# Nodino-CM4.net
KiCad netlist of a schematic drawn in EAGLE
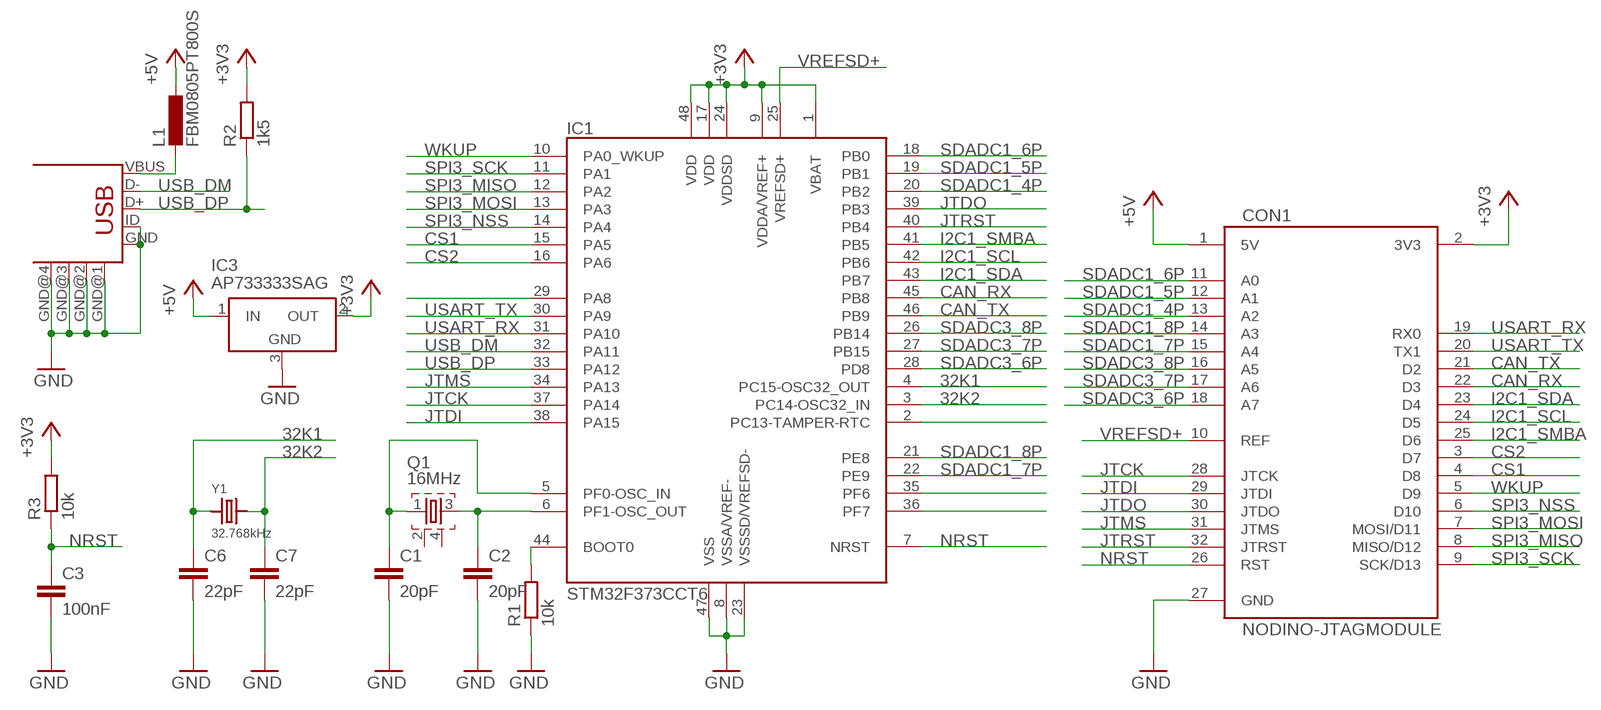
[diagram p0: schematic, sheet 1]

(export (version "E")
  (design (tool "Eeschema 10.0.6"))
  (components
    (comp (ref "C1")
      (value "20pF")
      (footprint "eagle-import:C0603K")
      (libsource (lib "eagle-import") (part "C-EUC0603K"))
    )
    (comp (ref "C2")
      (value "20pF")
      (footprint "eagle-import:C0603K")
      (libsource (lib "eagle-import") (part "C-EUC0603K"))
    )
    (comp (ref "C3")
      (value "100nF")
      (footprint "eagle-import:C0603K")
      (libsource (lib "eagle-import") (part "C-EUC0603K"))
    )
    (comp (ref "C6")
      (value "22pF")
      (footprint "eagle-import:C0603K")
      (libsource (lib "eagle-import") (part "C-EUC0603K"))
    )
    (comp (ref "C7")
      (value "22pF")
      (footprint "eagle-import:C0603K")
      (libsource (lib "eagle-import") (part "C-EUC0603K"))
    )
    (comp (ref "CON1")
      (value "NODINO-JTAGMODULE")
      (footprint "eagle-import:NODINO-JTAG-MOD")
      (libsource (lib "eagle-import") (part "NODINO-JTAGMODULE"))
    )
    (comp (ref "CON2")
      (value "USB-OTG_SHIELD")
      (footprint "eagle-import:USB-UAB-S1")
      (libsource (lib "eagle-import") (part "USB-OTG_SHIELD"))
    )
    (comp (ref "IC1")
      (value "STM32F373CCT6")
      (footprint "eagle-import:LQFP48")
      (libsource (lib "eagle-import") (part "STM32F373CCT6"))
    )
    (comp (ref "IC3")
      (value "AP733333SAG")
      (footprint "eagle-import:SOT23")
      (libsource (lib "eagle-import") (part "AP733333SAG"))
    )
    (comp (ref "L1")
      (value "FBM0805PT800S")
      (footprint "eagle-import:L0805")
      (libsource (lib "eagle-import") (part "L-EUL0805"))
    )
    (comp (ref "Q1")
      (value "16MHz")
      (footprint "eagle-import:FA-20H")
      (libsource (lib "eagle-import") (part "FA-20H"))
    )
    (comp (ref "R1")
      (value "10k")
      (footprint "eagle-import:R0603K")
      (libsource (lib "eagle-import") (part "R-EU_R0603K"))
    )
    (comp (ref "R2")
      (value "1k5")
      (footprint "eagle-import:R0603K")
      (libsource (lib "eagle-import") (part "R-EU_R0603K"))
    )
    (comp (ref "R3")
      (value "10k")
      (footprint "eagle-import:R0603K")
      (libsource (lib "eagle-import") (part "R-EU_R0603K"))
    )
    (comp (ref "Y1")
      (value "32.768kHz")
      (footprint "eagle-import:ABS07")
      (libsource (lib "eagle-import") (part "CRYSTAL.ABS07"))
    )
  )
  (nets
    (net (code "1") (name "+3V3") (class "Default")
      (node (ref "CON1") (pin "2") (pinfunction "3V3_2") (pintype "bidirectional"))
      (node (ref "IC1") (pin "1") (pinfunction "VBAT_1") (pintype "power_in"))
      (node (ref "IC1") (pin "17") (pinfunction "VDD_17") (pintype "power_in"))
      (node (ref "IC1") (pin "24") (pinfunction "VDDSD_24") (pintype "power_in"))
      (node (ref "IC1") (pin "48") (pinfunction "VDD_48") (pintype "power_in"))
      (node (ref "IC1") (pin "9") (pinfunction "VDDA/VREF+_9") (pintype "power_in"))
      (node (ref "IC3") (pin "2") (pinfunction "OUT_2") (pintype "output"))
      (node (ref "R2") (pin "2") (pinfunction "2_2") (pintype "passive"))
      (node (ref "R3") (pin "2") (pinfunction "2_2") (pintype "passive"))
    )
    (net (code "2") (name "+5V") (class "Default")
      (node (ref "CON1") (pin "1") (pinfunction "5V_1") (pintype "bidirectional"))
      (node (ref "IC3") (pin "1") (pinfunction "IN_1") (pintype "input"))
      (node (ref "L1") (pin "1") (pinfunction "1_1") (pintype "passive"))
    )
    (net (code "3") (name "/32K1") (class "Default")
      (node (ref "C6") (pin "1") (pinfunction "1_1") (pintype "passive"))
      (node (ref "IC1") (pin "4") (pinfunction "PC15-OSC32_OUT_4") (pintype "input"))
      (node (ref "Y1") (pin "1") (pinfunction "1_1") (pintype "passive"))
    )
    (net (code "4") (name "/32K2") (class "Default")
      (node (ref "C7") (pin "1") (pinfunction "1_1") (pintype "passive"))
      (node (ref "IC1") (pin "3") (pinfunction "PC14-OSC32_IN_3") (pintype "input"))
      (node (ref "Y1") (pin "2") (pinfunction "2_2") (pintype "passive"))
    )
    (net (code "5") (name "/CAN_RX") (class "Default")
      (node (ref "CON1") (pin "22") (pinfunction "D3_22") (pintype "bidirectional"))
      (node (ref "IC1") (pin "45") (pinfunction "PB8_45") (pintype "bidirectional"))
    )
    (net (code "6") (name "/CAN_TX") (class "Default")
      (node (ref "CON1") (pin "21") (pinfunction "D2_21") (pintype "bidirectional"))
      (node (ref "IC1") (pin "46") (pinfunction "PB9_46") (pintype "input"))
    )
    (net (code "7") (name "/CS1") (class "Default")
      (node (ref "CON1") (pin "4") (pinfunction "D8_4") (pintype "bidirectional"))
      (node (ref "IC1") (pin "15") (pinfunction "PA5_15") (pintype "bidirectional"))
    )
    (net (code "8") (name "/CS2") (class "Default")
      (node (ref "CON1") (pin "3") (pinfunction "D7_3") (pintype "bidirectional"))
      (node (ref "IC1") (pin "16") (pinfunction "PA6_16") (pintype "bidirectional"))
    )
    (net (code "9") (name "/I2C1_SCL") (class "Default")
      (node (ref "CON1") (pin "24") (pinfunction "D5_24") (pintype "bidirectional"))
      (node (ref "IC1") (pin "42") (pinfunction "PB6_42") (pintype "input"))
    )
    (net (code "10") (name "/I2C1_SDA") (class "Default")
      (node (ref "CON1") (pin "23") (pinfunction "D4_23") (pintype "bidirectional"))
      (node (ref "IC1") (pin "43") (pinfunction "PB7_43") (pintype "bidirectional"))
    )
    (net (code "11") (name "/I2C1_SMBA") (class "Default")
      (node (ref "CON1") (pin "25") (pinfunction "D6_25") (pintype "bidirectional"))
      (node (ref "IC1") (pin "41") (pinfunction "PB5_41") (pintype "input"))
    )
    (net (code "12") (name "/JTCK") (class "Default")
      (node (ref "CON1") (pin "28") (pinfunction "JTCK_28") (pintype "bidirectional"))
      (node (ref "IC1") (pin "37") (pinfunction "PA14_37") (pintype "bidirectional"))
    )
    (net (code "13") (name "/JTDI") (class "Default")
      (node (ref "CON1") (pin "29") (pinfunction "JTDI_29") (pintype "bidirectional"))
      (node (ref "IC1") (pin "38") (pinfunction "PA15_38") (pintype "bidirectional"))
    )
    (net (code "14") (name "/JTDO") (class "Default")
      (node (ref "CON1") (pin "30") (pinfunction "JTDO_30") (pintype "bidirectional"))
      (node (ref "IC1") (pin "39") (pinfunction "PB3_39") (pintype "bidirectional"))
    )
    (net (code "15") (name "/JTMS") (class "Default")
      (node (ref "CON1") (pin "31") (pinfunction "JTMS_31") (pintype "bidirectional"))
      (node (ref "IC1") (pin "34") (pinfunction "PA13_34") (pintype "bidirectional"))
    )
    (net (code "16") (name "/JTRST") (class "Default")
      (node (ref "CON1") (pin "32") (pinfunction "JTRST_32") (pintype "bidirectional"))
      (node (ref "IC1") (pin "40") (pinfunction "PB4_40") (pintype "bidirectional"))
    )
    (net (code "17") (name "/NRST") (class "Default")
      (node (ref "C3") (pin "1") (pinfunction "1_1") (pintype "passive"))
      (node (ref "CON1") (pin "26") (pinfunction "RST_26") (pintype "bidirectional"))
      (node (ref "IC1") (pin "7") (pinfunction "NRST_7") (pintype "input"))
      (node (ref "R3") (pin "1") (pinfunction "1_1") (pintype "passive"))
    )
    (net (code "18") (name "/SDADC1_4P") (class "Default")
      (node (ref "CON1") (pin "13") (pinfunction "A2_13") (pintype "bidirectional"))
      (node (ref "IC1") (pin "20") (pinfunction "PB2_20") (pintype "bidirectional"))
    )
    (net (code "19") (name "/SDADC1_5P") (class "Default")
      (node (ref "CON1") (pin "12") (pinfunction "A1_12") (pintype "bidirectional"))
      (node (ref "IC1") (pin "19") (pinfunction "PB1_19") (pintype "bidirectional"))
    )
    (net (code "20") (name "/SDADC1_6P") (class "Default")
      (node (ref "CON1") (pin "11") (pinfunction "A0_11") (pintype "bidirectional"))
      (node (ref "IC1") (pin "18") (pinfunction "PB0_18") (pintype "bidirectional"))
    )
    (net (code "21") (name "/SDADC1_7P") (class "Default")
      (node (ref "CON1") (pin "15") (pinfunction "A4_15") (pintype "bidirectional"))
      (node (ref "IC1") (pin "22") (pinfunction "PE9_22") (pintype "input"))
    )
    (net (code "22") (name "/SDADC1_8P") (class "Default")
      (node (ref "CON1") (pin "14") (pinfunction "A3_14") (pintype "bidirectional"))
      (node (ref "IC1") (pin "21") (pinfunction "PE8_21") (pintype "input"))
    )
    (net (code "23") (name "/SDADC3_6P") (class "Default")
      (node (ref "CON1") (pin "18") (pinfunction "A7_18") (pintype "bidirectional"))
      (node (ref "IC1") (pin "28") (pinfunction "PD8_28") (pintype "input"))
    )
    (net (code "24") (name "/SDADC3_7P") (class "Default")
      (node (ref "CON1") (pin "17") (pinfunction "A6_17") (pintype "bidirectional"))
      (node (ref "IC1") (pin "27") (pinfunction "PB15_27") (pintype "input"))
    )
    (net (code "25") (name "/SDADC3_8P") (class "Default")
      (node (ref "CON1") (pin "16") (pinfunction "A5_16") (pintype "bidirectional"))
      (node (ref "IC1") (pin "26") (pinfunction "PB14_26") (pintype "bidirectional"))
    )
    (net (code "26") (name "/SPI3_MISO") (class "Default")
      (node (ref "CON1") (pin "8") (pinfunction "MISO/D12_8") (pintype "bidirectional"))
      (node (ref "IC1") (pin "12") (pinfunction "PA2_12") (pintype "bidirectional"))
    )
    (net (code "27") (name "/SPI3_MOSI") (class "Default")
      (node (ref "CON1") (pin "7") (pinfunction "MOSI/D11_7") (pintype "bidirectional"))
      (node (ref "IC1") (pin "13") (pinfunction "PA3_13") (pintype "bidirectional"))
    )
    (net (code "28") (name "/SPI3_NSS") (class "Default")
      (node (ref "CON1") (pin "6") (pinfunction "D10_6") (pintype "bidirectional"))
      (node (ref "IC1") (pin "14") (pinfunction "PA4_14") (pintype "bidirectional"))
    )
    (net (code "29") (name "/SPI3_SCK") (class "Default")
      (node (ref "CON1") (pin "9") (pinfunction "SCK/D13_9") (pintype "bidirectional"))
      (node (ref "IC1") (pin "11") (pinfunction "PA1_11") (pintype "bidirectional"))
    )
    (net (code "30") (name "/USART_RX") (class "Default")
      (node (ref "CON1") (pin "19") (pinfunction "RX0_19") (pintype "bidirectional"))
      (node (ref "IC1") (pin "31") (pinfunction "PA10_31") (pintype "bidirectional"))
    )
    (net (code "31") (name "/USART_TX") (class "Default")
      (node (ref "CON1") (pin "20") (pinfunction "TX1_20") (pintype "bidirectional"))
      (node (ref "IC1") (pin "30") (pinfunction "PA9_30") (pintype "input"))
    )
    (net (code "32") (name "/USB_DM") (class "Default")
      (node (ref "CON2") (pin "D-") (pinfunction "D-_D-") (pintype "bidirectional"))
      (node (ref "IC1") (pin "32") (pinfunction "PA11_32") (pintype "bidirectional"))
    )
    (net (code "33") (name "/USB_DP") (class "Default")
      (node (ref "CON2") (pin "D+") (pinfunction "D+_D+") (pintype "bidirectional"))
      (node (ref "IC1") (pin "33") (pinfunction "PA12_33") (pintype "bidirectional"))
      (node (ref "R2") (pin "1") (pinfunction "1_1") (pintype "passive"))
    )
    (net (code "34") (name "/VREFSD+") (class "Default")
      (node (ref "CON1") (pin "10") (pinfunction "REF_10") (pintype "bidirectional"))
      (node (ref "IC1") (pin "25") (pinfunction "VREFSD+_25") (pintype "power_in"))
    )
    (net (code "35") (name "/WKUP") (class "Default")
      (node (ref "CON1") (pin "5") (pinfunction "D9_5") (pintype "bidirectional"))
      (node (ref "IC1") (pin "10") (pinfunction "PA0_WKUP_10") (pintype "bidirectional"))
    )
    (net (code "36") (name "GND") (class "Default")
      (node (ref "C1") (pin "2") (pinfunction "2_2") (pintype "passive"))
      (node (ref "C2") (pin "2") (pinfunction "2_2") (pintype "passive"))
      (node (ref "C3") (pin "2") (pinfunction "2_2") (pintype "passive"))
      (node (ref "C6") (pin "2") (pinfunction "2_2") (pintype "passive"))
      (node (ref "C7") (pin "2") (pinfunction "2_2") (pintype "passive"))
      (node (ref "CON1") (pin "27") (pinfunction "GND_27") (pintype "bidirectional"))
      (node (ref "CON2") (pin "GND") (pinfunction "GND_GND") (pintype "power_in"))
      (node (ref "CON2") (pin "GND@1") (pinfunction "GND_GND@1") (pintype "power_in"))
      (node (ref "CON2") (pin "GND@2") (pinfunction "GND_GND@2") (pintype "power_in"))
      (node (ref "CON2") (pin "GND@3") (pinfunction "GND_GND@3") (pintype "power_in"))
      (node (ref "CON2") (pin "GND@4") (pinfunction "GND_GND@4") (pintype "power_in"))
      (node (ref "CON2") (pin "ID") (pinfunction "ID_ID") (pintype "bidirectional"))
      (node (ref "IC1") (pin "23") (pinfunction "VSSSD/VREFSD-_23") (pintype "power_in"))
      (node (ref "IC1") (pin "47") (pinfunction "VSS_47") (pintype "power_in"))
      (node (ref "IC1") (pin "8") (pinfunction "VSSA/VREF-_8") (pintype "power_in"))
      (node (ref "IC3") (pin "3") (pinfunction "GND_3") (pintype "power_in"))
      (node (ref "R1") (pin "1") (pinfunction "1_1") (pintype "passive"))
    )
    (net (code "37") (name "Net-(CON2-PadVBUS)") (class "Default")
      (node (ref "CON2") (pin "VBUS") (pinfunction "VBUS_VBUS") (pintype "power_in"))
      (node (ref "L1") (pin "2") (pinfunction "2_2") (pintype "passive"))
    )
    (net (code "38") (name "Net-(IC1-BOOT0)") (class "Default")
      (node (ref "IC1") (pin "44") (pinfunction "BOOT0_44") (pintype "input"))
      (node (ref "R1") (pin "2") (pinfunction "2_2") (pintype "passive"))
    )
    (net (code "39") (name "Net-(IC1-PF0-OSC_IN)") (class "Default")
      (node (ref "C1") (pin "1") (pinfunction "1_1") (pintype "passive"))
      (node (ref "IC1") (pin "5") (pinfunction "PF0-OSC_IN_5") (pintype "input"))
      (node (ref "Q1") (pin "1") (pinfunction "1_1") (pintype "passive"))
    )
    (net (code "40") (name "Net-(IC1-PF1-OSC_OUT)") (class "Default")
      (node (ref "C2") (pin "1") (pinfunction "1_1") (pintype "passive"))
      (node (ref "IC1") (pin "6") (pinfunction "PF1-OSC_OUT_6") (pintype "input"))
      (node (ref "Q1") (pin "3") (pinfunction "3_3") (pintype "passive"))
    )
    (net (code "41") (name "unconnected-(IC1-PA8-Pad29)") (class "Default")
      (node (ref "IC1") (pin "29") (pinfunction "PA8_29") (pintype "bidirectional"))
    )
    (net (code "42") (name "unconnected-(IC1-PC13-TAMPER-RTC-Pad2)") (class "Default")
      (node (ref "IC1") (pin "2") (pinfunction "PC13-TAMPER-RTC_2") (pintype "input"))
    )
    (net (code "43") (name "unconnected-(IC1-PF6-Pad35)") (class "Default")
      (node (ref "IC1") (pin "35") (pinfunction "PF6_35") (pintype "input"))
    )
    (net (code "44") (name "unconnected-(IC1-PF7-Pad36)") (class "Default")
      (node (ref "IC1") (pin "36") (pinfunction "PF7_36") (pintype "input"))
    )
    (net (code "45") (name "unconnected-(Q1-Pad2)") (class "Default")
      (node (ref "Q1") (pin "2") (pinfunction "2_2") (pintype "passive"))
    )
    (net (code "46") (name "unconnected-(Q1-Pad4)") (class "Default")
      (node (ref "Q1") (pin "4") (pinfunction "4_4") (pintype "passive"))
    )
  )
)
